# IOT_nRF24L01_RELAY_TEST.net
KiCad netlist of a schematic drawn in Altium Designer
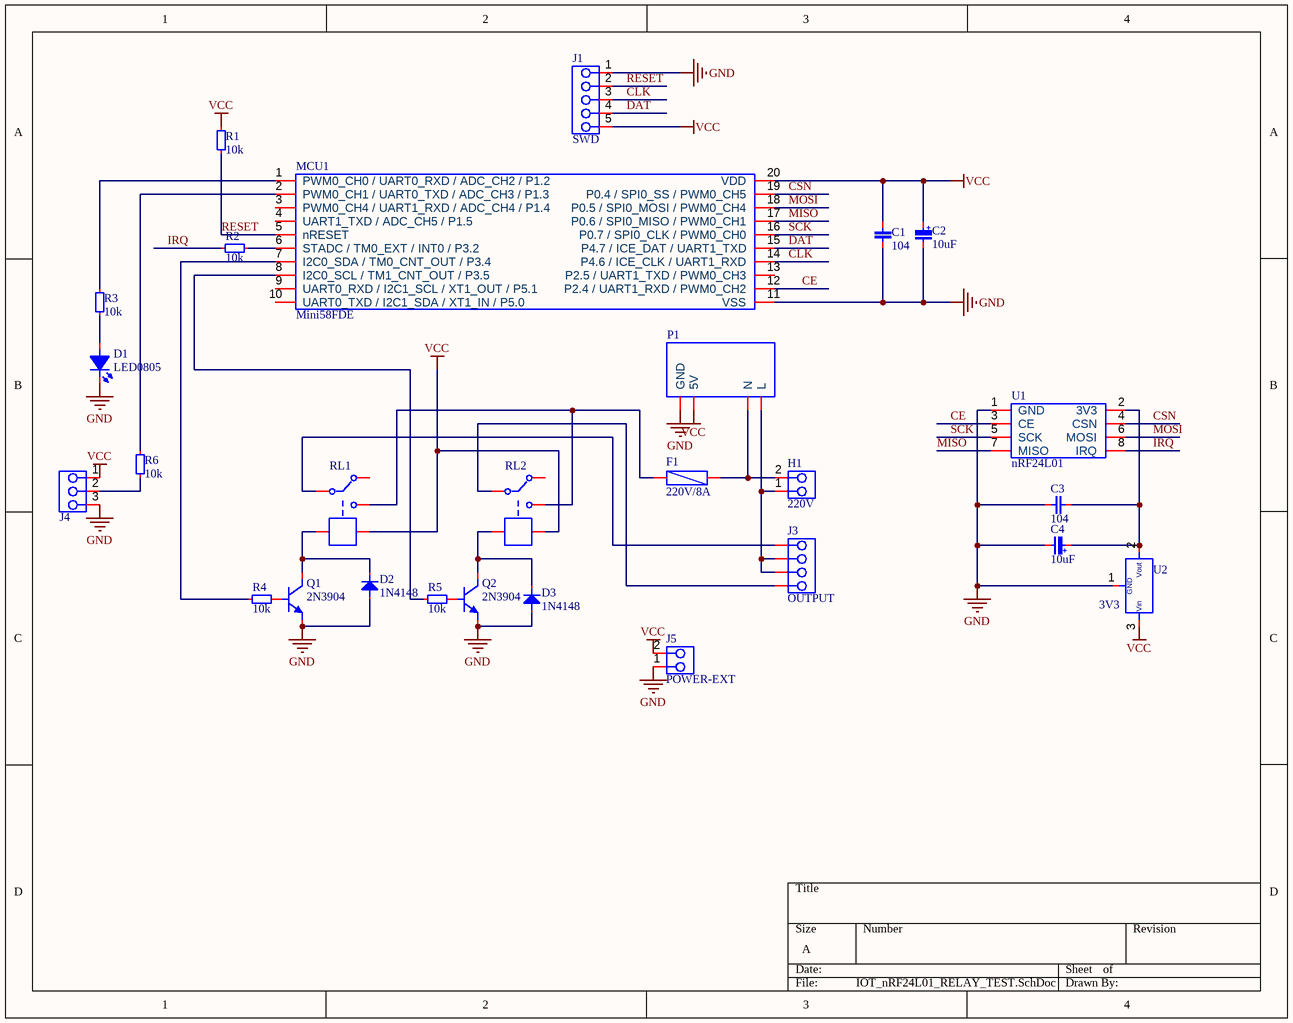
[diagram p0: IOT_nRF24L01_RELAY_TEST.SchDoc]

(export (version "E")
  (design (tool "Eeschema 10.0.6"))
  (components
    (comp (ref "C1") (value "104") (footprint "C0805") (libsource (lib "") (part "Capacitors(SMD)_1")))
    (comp (ref "C2")
      (value "10uF")
      (footprint "CAP_RAD_D05x11")
      (libsource (lib "") (part "Capacitor(Radian)_1"))
    )
    (comp (ref "C3")
      (value "104")
      (footprint "C1206")
      (libsource (lib "MyAltiumLibrary") (part "Capacitors(SMD)"))
    )
    (comp (ref "C4")
      (value "10uF")
      (footprint "CAP_RAD_D05x11")
      (libsource (lib "MyAltiumLibrary") (part "Capacitor(Radian)"))
    )
    (comp (ref "D1")
      (value "LED0805")
      (footprint "L0805RED")
      (libsource (lib "MyAltiumLibrary") (part "LED0805"))
    )
    (comp (ref "D2")
      (value "1N4148")
      (footprint "SOD-80")
      (description "The fast switching diode")
      (libsource (lib "MyAltiumLibrary") (part "Diode-1N4148"))
    )
    (comp (ref "D3")
      (value "1N4148")
      (footprint "SOD-80")
      (description "The fast switching diode")
      (libsource (lib "MyAltiumLibrary") (part "Diode-1N4148"))
    )
    (comp (ref "F1")
      (value "220V/8A")
      (footprint "FUSE_Bel_MJS_V")
      (libsource (lib "MyAltiumLibrary") (part "Fuse-Vertical"))
    )
    (comp (ref "H1")
      (value "220V")
      (footprint "TERMINAL-BLOCK-7.62MM -02PIN")
      (libsource (lib "MyAltiumLibrary") (part "TERMINAL-BLOCK-7.62MM-02PIN"))
    )
    (comp (ref "J1")
      (value "SWD")
      (footprint "HEADER-MALE-05PINS-2.54MM")
      (libsource (lib "MyAltiumLibrary") (part "HEADER-MALE-05PINS-2.54MM"))
    )
    (comp (ref "J3")
      (value "OUTPUT")
      (footprint "DG306-5.0-04P-12-00AH")
      (libsource (lib "MyAltiumLibrary") (part "DG306-5.0-04P-12-00AH"))
    )
    (comp (ref "J4")
      (value "HEADER-MALE-2.54MM")
      (footprint "HEADER-MALE-03PINS-2.54MM")
      (libsource (lib "MyAltiumLibrary") (part "HEADER-MALE-03PINS-2.54MM"))
    )
    (comp (ref "J5")
      (value "POWER-EXT")
      (footprint "HEADER-MALE-02PINS-2.54MM")
      (libsource (lib "MyAltiumLibrary") (part "HEADER-MALE-02PINS-2.54MM"))
    )
    (comp (ref "MCU1")
      (value "Mini58FDE")
      (footprint "TSSOP20_0.65_4.4")
      (description "Novoton 4Kb-RAM 32Kb-Flash")
      (libsource (lib "MyAltiumLibrary") (part "Mcu-Mini58FDE"))
    )
    (comp (ref "P1")
      (value "MODULE_5V_700mA")
      (footprint "MODULE_5V_700mA")
      (libsource (lib "MyAltiumLibrary") (part "SMPS_5V_700mA"))
    )
    (comp (ref "Q1")
      (value "2N3904")
      (footprint "SOT23-3")
      (libsource (lib "MyAltiumLibrary") (part "Transistor-2N3904 (SOT-23)"))
    )
    (comp (ref "Q2")
      (value "2N3904")
      (footprint "SOT23-3")
      (libsource (lib "MyAltiumLibrary") (part "Transistor-2N3904 (SOT-23)"))
    )
    (comp (ref "R1") (value "10k") (footprint "R0805") (libsource (lib "") (part "Resistors-SMD_1")))
    (comp (ref "R2")
      (value "10k")
      (footprint "R0805")
      (libsource (lib "MyAltiumLibrary") (part "Resistors-SMD"))
    )
    (comp (ref "R3") (value "10k") (footprint "R0805") (libsource (lib "") (part "Resistors-SMD_1")))
    (comp (ref "R4")
      (value "10k")
      (footprint "R0805")
      (libsource (lib "MyAltiumLibrary") (part "Resistors-SMD"))
    )
    (comp (ref "R5")
      (value "10k")
      (footprint "R0805")
      (libsource (lib "MyAltiumLibrary") (part "Resistors-SMD"))
    )
    (comp (ref "R6") (value "10k") (footprint "R0805") (libsource (lib "") (part "Resistors-SMD_1")))
    (comp (ref "RL1")
      (value "Relay-SONGLE-SRD-05VDC")
      (footprint "RELAY-SONGLE-SRD-05VDC_BLUE")
      (libsource (lib "MyAltiumLibrary") (part "Relay-SONGLE-SRD-05VDC"))
    )
    (comp (ref "RL2")
      (value "Relay-SONGLE-SRD-05VDC")
      (footprint "RELAY-SONGLE-SRD-05VDC_BLUE")
      (libsource (lib "MyAltiumLibrary") (part "Relay-SONGLE-SRD-05VDC"))
    )
    (comp (ref "U1")
      (value "nRF24L01")
      (footprint "nRF24L01")
      (libsource (lib "MyAltiumLibrary") (part "Module-nRF24L01"))
    )
    (comp (ref "U2")
      (value "3V3")
      (footprint "SOT223-3")
      (libsource (lib "MyAltiumLibrary") (part "Ic-AMS1117(SOT-223)"))
    )
  )
  (nets
    (net (code "1") (name "/CE") (class "Default")
      (node (ref "MCU1") (pin "12") (pinfunction "P2.4_/_UART1_RXD_/_PWM0_CH2_12") (pintype "passive"))
      (node (ref "U1") (pin "3") (pinfunction "CE_3") (pintype "passive"))
    )
    (net (code "2") (name "/CLK") (class "Default")
      (node (ref "J1") (pin "3") (pinfunction "3_3") (pintype "passive"))
      (node (ref "MCU1") (pin "14") (pinfunction "P4.6_/_ICE_CLK_/_UART1_RXD_14") (pintype "passive"))
    )
    (net (code "3") (name "/CSN") (class "Default")
      (node (ref "MCU1") (pin "19") (pinfunction "P0.4_/_SPI0_SS_/_PWM0_CH5_19") (pintype "passive"))
      (node (ref "U1") (pin "4") (pinfunction "CSN_4") (pintype "passive"))
    )
    (net (code "4") (name "/DAT") (class "Default")
      (node (ref "J1") (pin "4") (pinfunction "4_4") (pintype "passive"))
      (node (ref "MCU1") (pin "15") (pinfunction "P4.7_/_ICE_DAT_/_UART1_TXD_15") (pintype "passive"))
    )
    (net (code "5") (name "/IRQ") (class "Default")
      (node (ref "R2") (pin "1") (pinfunction "1_1") (pintype "passive"))
      (node (ref "U1") (pin "8") (pinfunction "IRQ_8") (pintype "passive"))
    )
    (net (code "6") (name "/MISO") (class "Default")
      (node (ref "MCU1") (pin "17") (pinfunction "P0.6_/_SPI0_MISO_/_PWM0_CH1_17") (pintype "passive"))
      (node (ref "U1") (pin "7") (pinfunction "MISO_7") (pintype "passive"))
    )
    (net (code "7") (name "/MOSI") (class "Default")
      (node (ref "MCU1") (pin "18") (pinfunction "P0.5_/_SPI0_MOSI_/_PWM0_CH4_18") (pintype "passive"))
      (node (ref "U1") (pin "6") (pinfunction "MOSI_6") (pintype "passive"))
    )
    (net (code "8") (name "/RESET") (class "Default")
      (node (ref "J1") (pin "2") (pinfunction "2_2") (pintype "passive"))
      (node (ref "MCU1") (pin "5") (pinfunction "nRESET_5") (pintype "passive"))
      (node (ref "R1") (pin "1") (pinfunction "1_1") (pintype "passive"))
    )
    (net (code "9") (name "/SCK") (class "Default")
      (node (ref "MCU1") (pin "16") (pinfunction "P0.7_/_SPI0_CLK_/_PWM0_CH0_16") (pintype "passive"))
      (node (ref "U1") (pin "5") (pinfunction "SCK_5") (pintype "passive"))
    )
    (net (code "10") (name "GND") (class "Default")
      (node (ref "C1") (pin "1") (pinfunction "1_1") (pintype "passive"))
      (node (ref "C2") (pin "2") (pinfunction "2_2") (pintype "passive"))
      (node (ref "C3") (pin "1") (pinfunction "1_1") (pintype "passive"))
      (node (ref "C4") (pin "2") (pinfunction "2_2") (pintype "passive"))
      (node (ref "D1") (pin "2") (pinfunction "K_2") (pintype "passive"))
      (node (ref "D2") (pin "1") (pinfunction "1_1") (pintype "passive"))
      (node (ref "D3") (pin "1") (pinfunction "1_1") (pintype "passive"))
      (node (ref "J1") (pin "1") (pinfunction "1_1") (pintype "passive"))
      (node (ref "J4") (pin "3") (pinfunction "3_3") (pintype "passive"))
      (node (ref "J5") (pin "1") (pinfunction "1_1") (pintype "passive"))
      (node (ref "MCU1") (pin "11") (pinfunction "VSS_11") (pintype "passive"))
      (node (ref "P1") (pin "4") (pinfunction "GND_4") (pintype "passive"))
      (node (ref "Q1") (pin "2") (pinfunction "E_2") (pintype "passive"))
      (node (ref "Q2") (pin "2") (pinfunction "E_2") (pintype "passive"))
      (node (ref "U1") (pin "1") (pinfunction "GND_1") (pintype "passive"))
      (node (ref "U2") (pin "1") (pinfunction "1_1") (pintype "passive"))
    )
    (net (code "11") (name "Net-(D1-A)") (class "Default")
      (node (ref "D1") (pin "1") (pinfunction "A_1") (pintype "passive"))
      (node (ref "R3") (pin "1") (pinfunction "1_1") (pintype "passive"))
    )
    (net (code "12") (name "Net-(F1-Pad1)") (class "Default")
      (node (ref "F1") (pin "1") (pinfunction "1_1") (pintype "passive"))
      (node (ref "RL1") (pin "4") (pinfunction "4_4") (pintype "passive"))
      (node (ref "RL2") (pin "4") (pinfunction "4_4") (pintype "passive"))
    )
    (net (code "13") (name "Net-(J3-Pad1)") (class "Default")
      (node (ref "J3") (pin "1") (pinfunction "1_1") (pintype "passive"))
      (node (ref "RL2") (pin "2") (pinfunction "2_2") (pintype "passive"))
    )
    (net (code "14") (name "Net-(J3-Pad4)") (class "Default")
      (node (ref "J3") (pin "4") (pinfunction "4_4") (pintype "passive"))
      (node (ref "RL1") (pin "2") (pinfunction "2_2") (pintype "passive"))
    )
    (net (code "15") (name "Net-(J4-Pad2)") (class "Default")
      (node (ref "J4") (pin "2") (pinfunction "2_2") (pintype "passive"))
      (node (ref "R6") (pin "1") (pinfunction "1_1") (pintype "passive"))
    )
    (net (code "16") (name "Net-(MCU1-I2C0_SCL_{slash}_TM1_CNT_OUT_{slash}_P3.5)") (class "Default")
      (node (ref "MCU1") (pin "8") (pinfunction "I2C0_SCL_/_TM1_CNT_OUT_/_P3.5_8") (pintype "passive"))
      (node (ref "R5") (pin "1") (pinfunction "1_1") (pintype "passive"))
    )
    (net (code "17") (name "Net-(MCU1-I2C0_SDA_{slash}_TM0_CNT_OUT_{slash}_P3.4)") (class "Default")
      (node (ref "MCU1") (pin "7") (pinfunction "I2C0_SDA_/_TM0_CNT_OUT_/_P3.4_7") (pintype "passive"))
      (node (ref "R4") (pin "1") (pinfunction "1_1") (pintype "passive"))
    )
    (net (code "18") (name "Net-(MCU1-PWM0_CH0_{slash}_UART0_RXD_{slash}_ADC_CH2_{slash}_P1.2)") (class "Default")
      (node (ref "MCU1") (pin "1") (pinfunction "PWM0_CH0_/_UART0_RXD_/_ADC_CH2_/_P1.2_1") (pintype "passive"))
      (node (ref "R3") (pin "2") (pinfunction "2_2") (pintype "passive"))
    )
    (net (code "19") (name "Net-(MCU1-PWM0_CH1_{slash}_UART0_TXD_{slash}_ADC_CH3_{slash}_P1.3)") (class "Default")
      (node (ref "MCU1") (pin "2") (pinfunction "PWM0_CH1_/_UART0_TXD_/_ADC_CH3_/_P1.3_2") (pintype "passive"))
      (node (ref "R6") (pin "2") (pinfunction "2_2") (pintype "passive"))
    )
    (net (code "20") (name "Net-(MCU1-STADC_{slash}_TM0_EXT_{slash}_INT0_{slash}_P3.2)") (class "Default")
      (node (ref "MCU1") (pin "6") (pinfunction "STADC_/_TM0_EXT_/_INT0_/_P3.2_6") (pintype "passive"))
      (node (ref "R2") (pin "2") (pinfunction "2_2") (pintype "passive"))
    )
    (net (code "21") (name "Net-(P1-L)") (class "Default")
      (node (ref "H1") (pin "1") (pinfunction "1_1") (pintype "passive"))
      (node (ref "J3") (pin "2") (pinfunction "2_2") (pintype "passive"))
      (node (ref "J3") (pin "3") (pinfunction "3_3") (pintype "passive"))
      (node (ref "P1") (pin "1") (pinfunction "L_1") (pintype "passive"))
    )
    (net (code "22") (name "Net-(P1-N)") (class "Default")
      (node (ref "F1") (pin "2") (pinfunction "2_2") (pintype "passive"))
      (node (ref "H1") (pin "2") (pinfunction "2_2") (pintype "passive"))
      (node (ref "P1") (pin "2") (pinfunction "N_2") (pintype "passive"))
    )
    (net (code "23") (name "Net-(Q1-B)") (class "Default")
      (node (ref "Q1") (pin "1") (pinfunction "B_1") (pintype "passive"))
      (node (ref "R4") (pin "2") (pinfunction "2_2") (pintype "passive"))
    )
    (net (code "24") (name "Net-(Q1-C)") (class "Default")
      (node (ref "D2") (pin "2") (pinfunction "2_2") (pintype "passive"))
      (node (ref "Q1") (pin "3") (pinfunction "C_3") (pintype "passive"))
      (node (ref "RL1") (pin "1") (pinfunction "1_1") (pintype "passive"))
    )
    (net (code "25") (name "Net-(Q2-B)") (class "Default")
      (node (ref "Q2") (pin "1") (pinfunction "B_1") (pintype "passive"))
      (node (ref "R5") (pin "2") (pinfunction "2_2") (pintype "passive"))
    )
    (net (code "26") (name "Net-(Q2-C)") (class "Default")
      (node (ref "D3") (pin "2") (pinfunction "2_2") (pintype "passive"))
      (node (ref "Q2") (pin "3") (pinfunction "C_3") (pintype "passive"))
      (node (ref "RL2") (pin "1") (pinfunction "1_1") (pintype "passive"))
    )
    (net (code "27") (name "Net-(U1-3V3)") (class "Default")
      (node (ref "C3") (pin "2") (pinfunction "2_2") (pintype "passive"))
      (node (ref "C4") (pin "1") (pinfunction "1_1") (pintype "passive"))
      (node (ref "U1") (pin "2") (pinfunction "3V3_2") (pintype "passive"))
      (node (ref "U2") (pin "2") (pinfunction "2_2") (pintype "passive"))
    )
    (net (code "28") (name "VCC") (class "Default")
      (node (ref "C1") (pin "2") (pinfunction "2_2") (pintype "passive"))
      (node (ref "C2") (pin "1") (pinfunction "1_1") (pintype "passive"))
      (node (ref "J1") (pin "5") (pinfunction "5_5") (pintype "passive"))
      (node (ref "J4") (pin "1") (pinfunction "1_1") (pintype "passive"))
      (node (ref "J5") (pin "2") (pinfunction "2_2") (pintype "passive"))
      (node (ref "MCU1") (pin "20") (pinfunction "VDD_20") (pintype "passive"))
      (node (ref "P1") (pin "3") (pinfunction "5V_3") (pintype "passive"))
      (node (ref "R1") (pin "2") (pinfunction "2_2") (pintype "passive"))
      (node (ref "RL1") (pin "3") (pinfunction "3_3") (pintype "passive"))
      (node (ref "RL2") (pin "3") (pinfunction "3_3") (pintype "passive"))
      (node (ref "U2") (pin "3") (pinfunction "3_3") (pintype "passive"))
    )
    (net (code "29") (name "unconnected-(MCU1-P2.5_{slash}_UART1_TXD_{slash}_PWM0_CH3-Pad13)") (class "Default")
      (node (ref "MCU1") (pin "13") (pinfunction "P2.5_/_UART1_TXD_/_PWM0_CH3_13") (pintype "passive"))
    )
    (net (code "30") (name "unconnected-(MCU1-PWM0_CH4_{slash}_UART1_RXD_{slash}_ADC_CH4_{slash}_P1.4-Pad3)") (class "Default")
      (node (ref "MCU1") (pin "3") (pinfunction "PWM0_CH4_/_UART1_RXD_/_ADC_CH4_/_P1.4_3") (pintype "passive"))
    )
    (net (code "31") (name "unconnected-(MCU1-UART0_RXD_{slash}_I2C1_SCL_{slash}_XT1_OUT_{slash}_P5.1-Pad9)") (class "Default")
      (node (ref "MCU1") (pin "9") (pinfunction "UART0_RXD_/_I2C1_SCL_/_XT1_OUT_/_P5.1_9") (pintype "passive"))
    )
    (net (code "32") (name "unconnected-(MCU1-UART0_TXD_{slash}_I2C1_SDA_{slash}_XT1_IN_{slash}_P5.0-Pad10)") (class "Default")
      (node (ref "MCU1") (pin "10") (pinfunction "UART0_TXD_/_I2C1_SDA_/_XT1_IN_/_P5.0_10") (pintype "passive"))
    )
    (net (code "33") (name "unconnected-(MCU1-UART1_TXD_{slash}_ADC_CH5_{slash}_P1.5-Pad4)") (class "Default")
      (node (ref "MCU1") (pin "4") (pinfunction "UART1_TXD_/_ADC_CH5_/_P1.5_4") (pintype "passive"))
    )
    (net (code "34") (name "unconnected-(RL1-Pad5)") (class "Default")
      (node (ref "RL1") (pin "5") (pinfunction "5_5") (pintype "passive"))
    )
    (net (code "35") (name "unconnected-(RL2-Pad5)") (class "Default")
      (node (ref "RL2") (pin "5") (pinfunction "5_5") (pintype "passive"))
    )
  )
)
